# Sch_Dr_EEPROM.net
KiCad netlist of a schematic drawn in Altium Designer
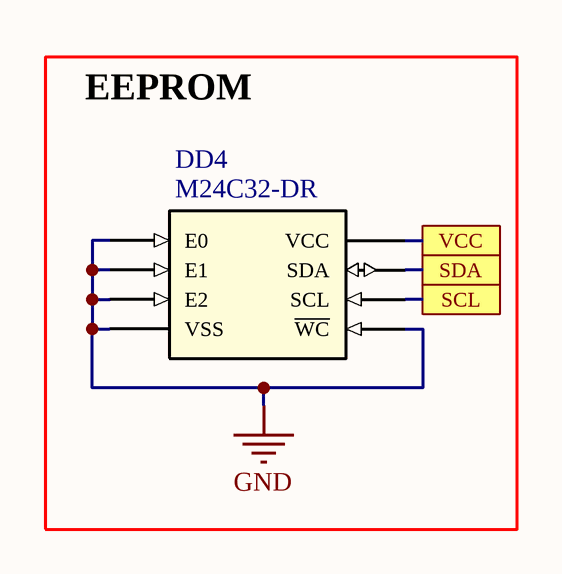
[diagram p0: Sch_Dr_EEPROM .SchDoc]

(export (version "E")
  (design (tool "Eeschema 10.0.6"))
  (components
    (comp (ref "DD4")
      (value "M24C32-DR")
      (footprint "TSSOP-8")
      (description "EEPROM Memory IC 32Kb (4K x 8) I²C 1 MHz 450 ns")
      (libsource (lib "Dr_lib") (part "M24C32-DR"))
    )
  )
  (nets
    (net (code "1") (name "/SCL") (class "Default")
      (node (ref "DD4") (pin "6") (pinfunction "SCL_6") (pintype "input"))
    )
    (net (code "2") (name "/SDA") (class "Default")
      (node (ref "DD4") (pin "5") (pinfunction "SDA_5") (pintype "bidirectional"))
    )
    (net (code "3") (name "/VCC") (class "Default")
      (node (ref "DD4") (pin "8") (pinfunction "VCC_8") (pintype "passive"))
    )
    (net (code "4") (name "GND") (class "Default")
      (node (ref "DD4") (pin "1") (pinfunction "E0_1") (pintype "input"))
      (node (ref "DD4") (pin "2") (pinfunction "E1_2") (pintype "input"))
      (node (ref "DD4") (pin "3") (pinfunction "E2_3") (pintype "input"))
      (node (ref "DD4") (pin "4") (pinfunction "VSS_4") (pintype "passive"))
      (node (ref "DD4") (pin "7") (pinfunction "~{WC}_7") (pintype "input"))
    )
  )
)
